# TKNTN.net
KiCad netlist of a schematic drawn in Altium Designer
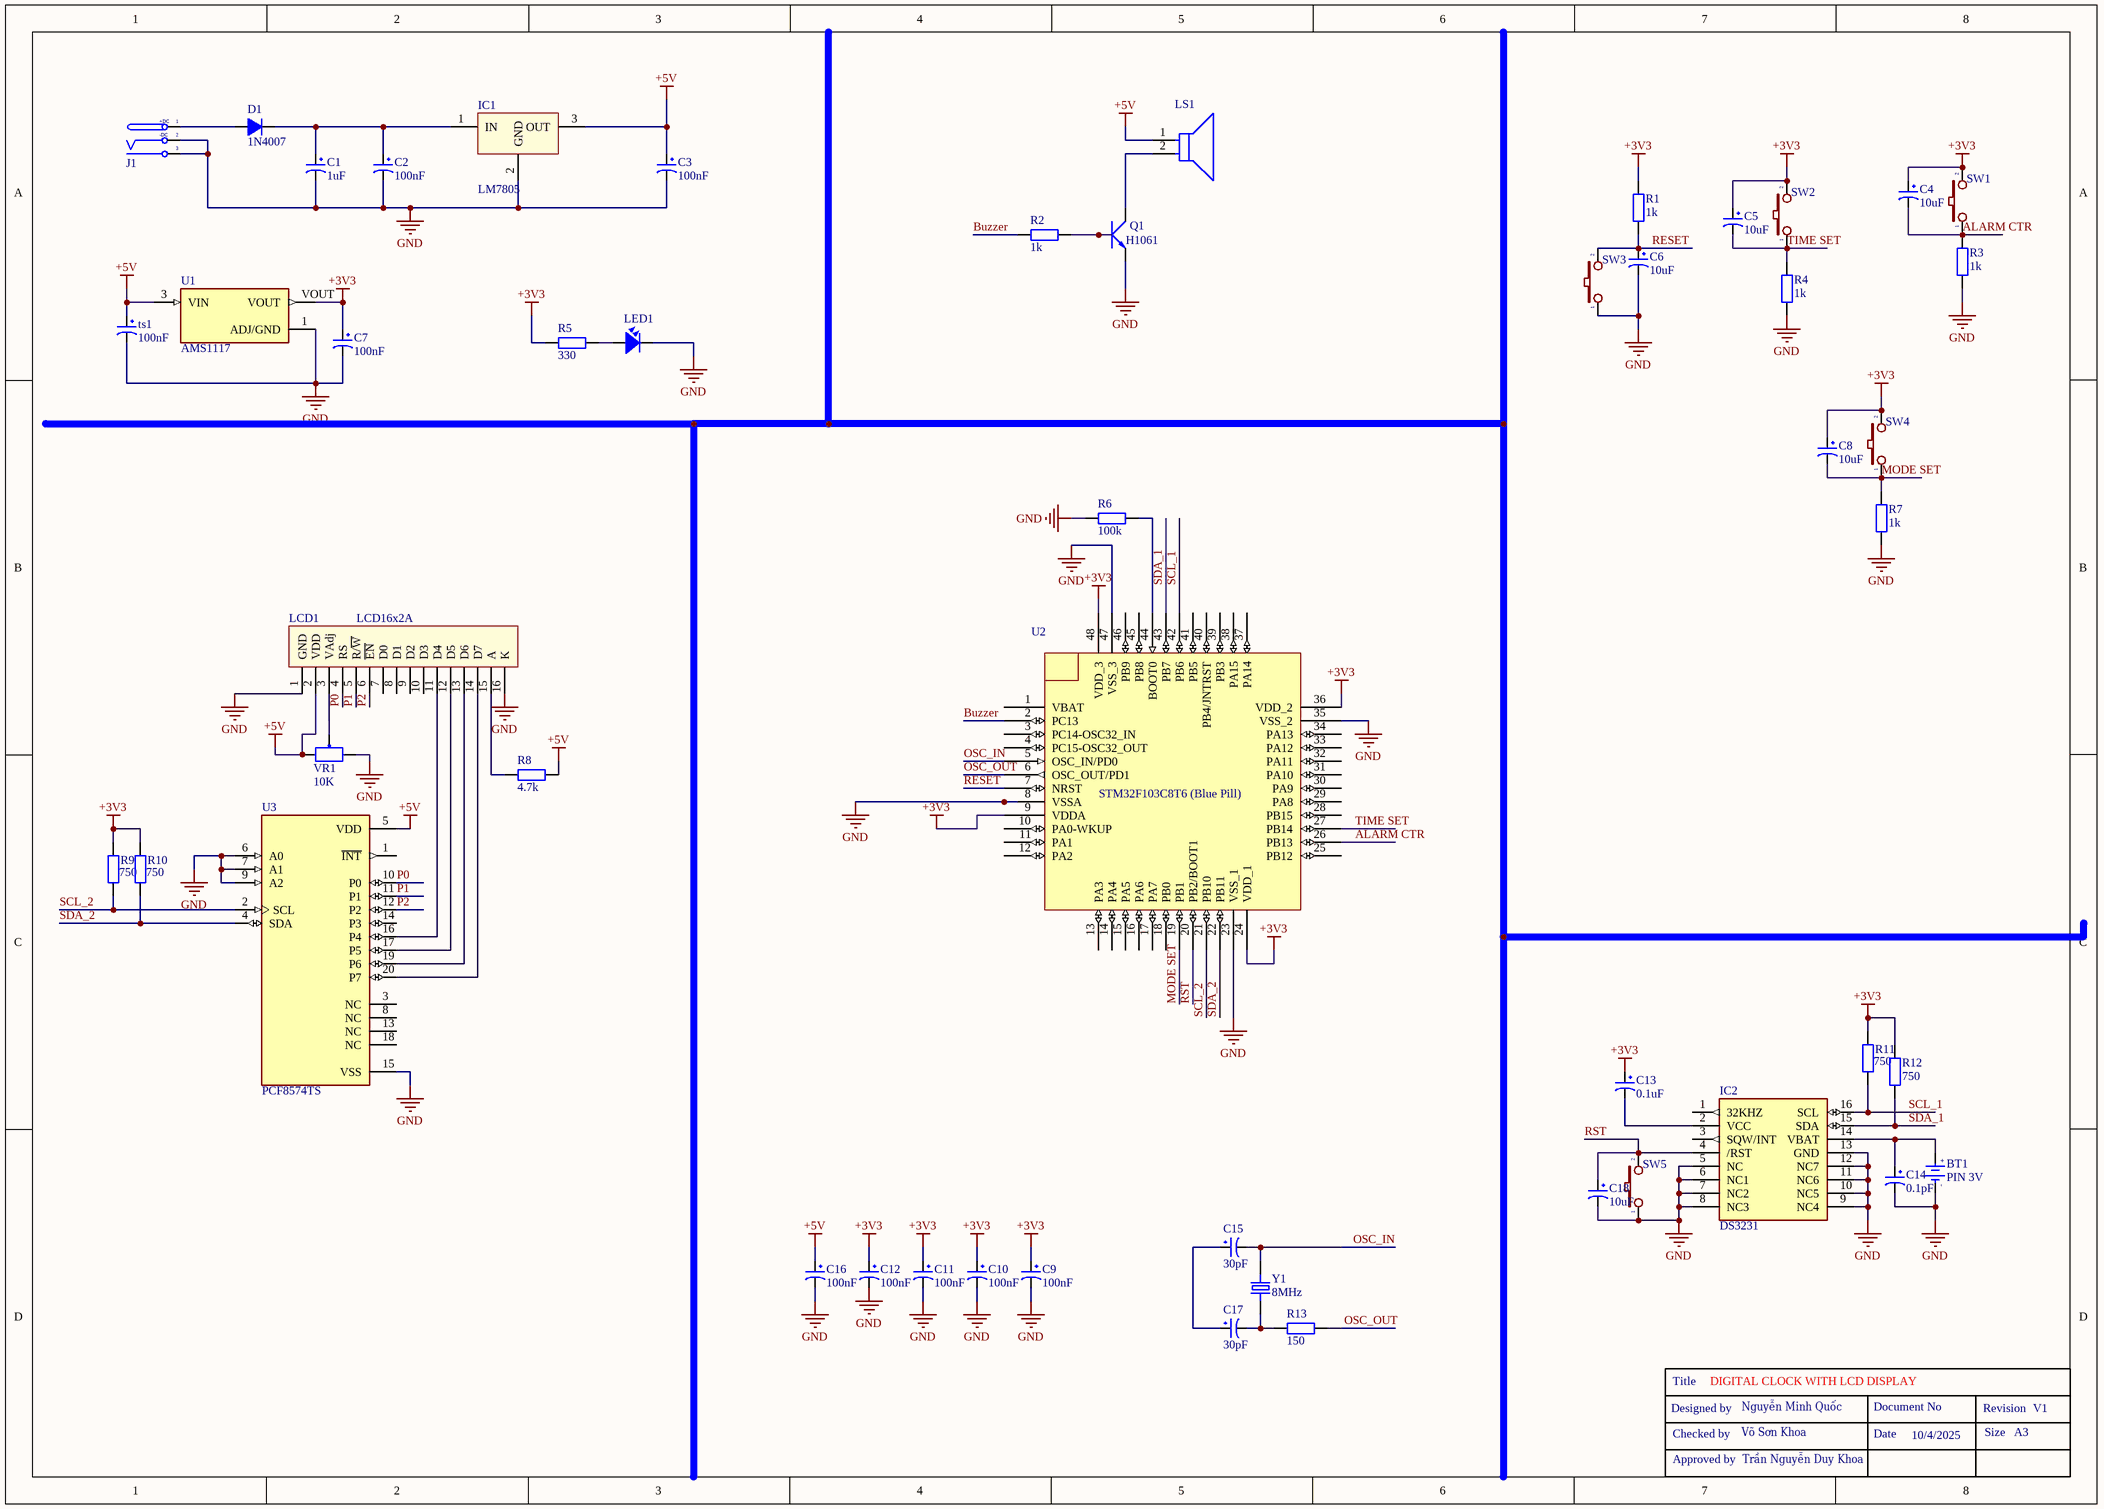
[diagram p0: TKNTN.SchDoc]

(export (version "E")
  (design (tool "Eeschema 10.0.6"))
  (components
    (comp (ref "*") (value "Component_2") (libsource (lib "Schlib1") (part "Component_2")))
    (comp (ref "BT1")
      (value "PIN 3V")
      (footprint "PIN3V")
      (description "Battery 3VDC")
      (libsource (lib "syhaunguyen") (part "PIN 3V"))
    )
    (comp (ref "C1")
      (value "1uF")
      (footprint "CP1/2")
      (description "Cap P  0,1uF < 22uF , 16 - 50V")
      (libsource (lib "syhaunguyen") (part "CP1"))
    )
    (comp (ref "C2")
      (value "100nF")
      (footprint "CP1/2")
      (description "Cap P  0,1uF < 22uF , 16 - 50V")
      (libsource (lib "syhaunguyen") (part "CP1"))
    )
    (comp (ref "C3")
      (value "100nF")
      (footprint "CP1/2")
      (description "Cap P  0,1uF < 22uF , 16 - 50V")
      (libsource (lib "syhaunguyen") (part "CP1"))
    )
    (comp (ref "C4")
      (value "10uF")
      (footprint "CP1/2")
      (description "Cap P  0,1uF < 22uF , 16 - 50V")
      (libsource (lib "syhaunguyen") (part "CP1"))
    )
    (comp (ref "C5")
      (value "10uF")
      (footprint "CP1/2")
      (description "Cap P  0,1uF < 22uF , 16 - 50V")
      (libsource (lib "syhaunguyen") (part "CP1"))
    )
    (comp (ref "C6")
      (value "10uF")
      (footprint "CP1/2")
      (description "Cap P  0,1uF < 22uF , 16 - 50V")
      (libsource (lib "syhaunguyen") (part "CP1"))
    )
    (comp (ref "C7")
      (value "100nF")
      (footprint "CP1/2")
      (description "Cap P  0,1uF < 22uF , 16 - 50V")
      (libsource (lib "syhaunguyen") (part "CP1"))
    )
    (comp (ref "C8")
      (value "10uF")
      (footprint "CP1/2")
      (description "Cap P  0,1uF < 22uF , 16 - 50V")
      (libsource (lib "syhaunguyen") (part "CP1"))
    )
    (comp (ref "C9")
      (value "100nF")
      (footprint "CP1/2")
      (description "Cap P  0,1uF < 22uF , 16 - 50V")
      (libsource (lib "syhaunguyen") (part "CP1"))
    )
    (comp (ref "C10")
      (value "100nF")
      (footprint "CP1/2")
      (description "Cap P  0,1uF < 22uF , 16 - 50V")
      (libsource (lib "syhaunguyen") (part "CP1"))
    )
    (comp (ref "C11")
      (value "100nF")
      (footprint "CP1/2")
      (description "Cap P  0,1uF < 22uF , 16 - 50V")
      (libsource (lib "syhaunguyen") (part "CP1"))
    )
    (comp (ref "C12")
      (value "100nF")
      (footprint "CP1/2")
      (description "Cap P  0,1uF < 22uF , 16 - 50V")
      (libsource (lib "syhaunguyen") (part "CP1"))
    )
    (comp (ref "C13")
      (value "0.1uF")
      (footprint "CP1/2")
      (description "Cap P  0,1uF < 22uF , 16 - 50V")
      (libsource (lib "syhaunguyen") (part "CP1"))
    )
    (comp (ref "C14")
      (value "0.1pF")
      (footprint "CP1/2")
      (description "Cap P  0,1uF < 22uF , 16 - 50V")
      (libsource (lib "syhaunguyen") (part "CP1"))
    )
    (comp (ref "C15")
      (value "30pF")
      (footprint "CP1/2")
      (description "Cap P  0,1uF < 22uF , 16 - 50V")
      (libsource (lib "") (part "CP1_1"))
    )
    (comp (ref "C16")
      (value "100nF")
      (footprint "CP1/2")
      (description "Cap P  0,1uF < 22uF , 16 - 50V")
      (libsource (lib "syhaunguyen") (part "CP1"))
    )
    (comp (ref "C17")
      (value "30pF")
      (footprint "CP1/2")
      (description "Cap P  0,1uF < 22uF , 16 - 50V")
      (libsource (lib "") (part "CP1_1"))
    )
    (comp (ref "C18")
      (value "10uF")
      (footprint "CP1/2")
      (description "Cap P  0,1uF < 22uF , 16 - 50V")
      (libsource (lib "syhaunguyen") (part "CP1"))
    )
    (comp (ref "D1")
      (value "1N4007")
      (footprint "D1A")
      (description "Diode 1A")
      (libsource (lib "syhaunguyen") (part "D1A"))
    )
    (comp (ref "IC1")
      (value "LM7805")
      (footprint "QTO-220")
      (description "On ap +, from + 5 to + 24VDC")
      (libsource (lib "syhaunguyen") (part "LM78xx"))
    )
    (comp (ref "IC2")
      (value "DS3231")
      (footprint "DS3231:SO16W")
      (description "Real Time Clock (RTC) IC Clock/Calendar - IÂ²C, 2-Wire Serial 8-SOIC (0.154, 3.90mm Width)")
      (fields (field (name "MF") "Maxim Integrated"))
      (libsource (lib "*") (part "DS3231"))
    )
    (comp (ref "J1")
      (value "JACK DC 5MM")
      (footprint "JACK DC 5MM")
      (libsource (lib "Cty1") (part "JACK DC 5MM"))
    )
    (comp (ref "LCD1")
      (value "LCD16x2A")
      (footprint "LCD16X2")
      (description "LCD dipslay 16 char, 2 line")
      (libsource (lib "my Library") (part "LCD16x2"))
    )
    (comp (ref "LED1")
      (value "LED")
      (footprint "LED-3")
      (description "LED Single colour Green and Red")
      (libsource (lib "syhaunguyen") (part "LED"))
    )
    (comp (ref "LS1")
      (value "PKM13EPYH4000-A0")
      (footprint "FP-PKM13EPYH4000-A0-MFG")
      (description "AUDIO PIEZO TRANSDUCER 30V TH")
      (libsource (lib "Altium Content Vault") (part "5f581d31613f872430949aa526fd155"))
    )
    (comp (ref "Q1")
      (value "H1061")
      (footprint "QTO-220")
      (description "P 1W, BCE")
      (libsource (lib "syhaunguyen") (part "NPN_BCE"))
    )
    (comp (ref "R1")
      (value "1k")
      (footprint "R1/4W")
      (description "Resistor 1/4W")
      (libsource (lib "syhaunguyen") (part "R1/4W"))
    )
    (comp (ref "R2")
      (value "1k")
      (footprint "R1/4W")
      (description "Resistor 1/4W")
      (libsource (lib "syhaunguyen") (part "R1/4W"))
    )
    (comp (ref "R3")
      (value "1k")
      (footprint "R1/4W")
      (description "Resistor 1/4W")
      (libsource (lib "syhaunguyen") (part "R1/4W"))
    )
    (comp (ref "R4")
      (value "1k")
      (footprint "R1/4W")
      (description "Resistor 1/4W")
      (libsource (lib "syhaunguyen") (part "R1/4W"))
    )
    (comp (ref "R5")
      (value "330")
      (footprint "R1/4W")
      (description "Resistor 1/4W")
      (libsource (lib "syhaunguyen") (part "R1/4W"))
    )
    (comp (ref "R6")
      (value "100k")
      (footprint "R1/4W")
      (description "Resistor 1/4W")
      (libsource (lib "syhaunguyen") (part "R1/4W"))
    )
    (comp (ref "R7")
      (value "1k")
      (footprint "R1/4W")
      (description "Resistor 1/4W")
      (libsource (lib "syhaunguyen") (part "R1/4W"))
    )
    (comp (ref "R8")
      (value "4.7k")
      (footprint "R1/4W")
      (description "Resistor 1/4W")
      (libsource (lib "syhaunguyen") (part "R1/4W"))
    )
    (comp (ref "R9")
      (value "750")
      (footprint "R1/4W")
      (description "Resistor 1/4W")
      (libsource (lib "syhaunguyen") (part "R1/4W"))
    )
    (comp (ref "R10")
      (value "750")
      (footprint "R1/4W")
      (description "Resistor 1/4W")
      (libsource (lib "syhaunguyen") (part "R1/4W"))
    )
    (comp (ref "R11")
      (value "750")
      (footprint "R1/4W")
      (description "Resistor 1/4W")
      (libsource (lib "syhaunguyen") (part "R1/4W"))
    )
    (comp (ref "R12")
      (value "750")
      (footprint "R1/4W")
      (description "Resistor 1/4W")
      (libsource (lib "syhaunguyen") (part "R1/4W"))
    )
    (comp (ref "R13")
      (value "150")
      (footprint "R1/4W")
      (description "Resistor 1/4W")
      (libsource (lib "syhaunguyen") (part "R1/4W"))
    )
    (comp (ref "SW1")
      (value "ALARM CTR")
      (footprint "SW2")
      (description "Switch button 2 pin")
      (libsource (lib "Cty1") (part "SW2"))
    )
    (comp (ref "SW2")
      (value "TIME SET")
      (footprint "SW2")
      (description "Switch button 2 pin")
      (libsource (lib "Cty1") (part "SW2"))
    )
    (comp (ref "SW3")
      (value "RESET")
      (footprint "SW2")
      (description "Switch button 2 pin")
      (libsource (lib "Cty1") (part "SW2"))
    )
    (comp (ref "SW4")
      (value "MODE SET")
      (footprint "SW2")
      (description "Switch button 2 pin")
      (libsource (lib "Cty1") (part "SW2"))
    )
    (comp (ref "SW5")
      (value "RST DS3221")
      (footprint "SW2")
      (description "Switch button 2 pin")
      (libsource (lib "Cty1") (part "SW2"))
    )
    (comp (ref "ts1")
      (value "100nF")
      (footprint "CP1/2")
      (description "Cap P  0,1uF < 22uF , 16 - 50V")
      (libsource (lib "syhaunguyen") (part "CP1"))
    )
    (comp (ref "U1")
      (value "AMS1117")
      (footprint "AMS1117:SOT229P700X180-4N")
      (description "1A LOW DROPOUT VOLTAGE REGULATOR SOT-223")
      (fields (field (name "MF") "Advanced Monolithic Systems"))
      (libsource (lib "*") (part "AMS1117"))
    )
    (comp (ref "U2")
      (value "STM32F103C8T6 (Blue Pill)")
      (footprint "STM32F103RC_TSQFP")
      (description "STM32 ARM-based 32-bit MCU with 64 Kbytes Flash, 48-pin LQFP, Industrial Temperature")
      (fields (field (name "PUBLISHER") "Altium Limited"))
      (libsource (lib "my Library") (part "STM32F103xx_LQFP48"))
    )
    (comp (ref "U3")
      (value "PCF8574TS")
      (footprint "PCF8574TS:SOP65P640X150-20N")
      (description "I/O Expander 8 IÂ²C 100 kHz 20-SSOP")
      (fields (field (name "MF") "NXP USA"))
      (libsource (lib "*") (part "PCF8574TS"))
    )
    (comp (ref "VR1")
      (value "10K")
      (footprint "VR")
      (description "Var Resistor")
      (libsource (lib "syhaunguyen") (part "VR"))
    )
    (comp (ref "Y1")
      (value "8MHz")
      (footprint "ECS_240_0001_18_1X:XTAL_ECS-200-20-1X")
      (description "Crystals / Oscillators / Resonators 24.00014MHz 18pF")
      (fields (field (name "MF") "ECS International") (field (name "MP") "ECS-240.0001-18-1X"))
      (libsource (lib "*") (part "ECS-240.0001-18-1X"))
    )
  )
  (nets
    (net (code "1") (name "+3V3") (class "Default")
      (node (ref "C10") (pin "1") (pinfunction "1_1") (pintype "passive"))
      (node (ref "C11") (pin "1") (pinfunction "1_1") (pintype "passive"))
      (node (ref "C12") (pin "1") (pinfunction "1_1") (pintype "passive"))
      (node (ref "C13") (pin "1") (pinfunction "1_1") (pintype "passive"))
      (node (ref "C4") (pin "1") (pinfunction "1_1") (pintype "passive"))
      (node (ref "C5") (pin "1") (pinfunction "1_1") (pintype "passive"))
      (node (ref "C7") (pin "1") (pinfunction "1_1") (pintype "passive"))
      (node (ref "C8") (pin "1") (pinfunction "1_1") (pintype "passive"))
      (node (ref "C9") (pin "1") (pinfunction "1_1") (pintype "passive"))
      (node (ref "R1") (pin "2") (pinfunction "2_2") (pintype "passive"))
      (node (ref "R10") (pin "2") (pinfunction "2_2") (pintype "passive"))
      (node (ref "R11") (pin "2") (pinfunction "2_2") (pintype "passive"))
      (node (ref "R12") (pin "2") (pinfunction "2_2") (pintype "passive"))
      (node (ref "R5") (pin "1") (pinfunction "1_1") (pintype "passive"))
      (node (ref "R9") (pin "2") (pinfunction "2_2") (pintype "passive"))
      (node (ref "SW1") (pin "2") (pinfunction "2_2") (pintype "passive"))
      (node (ref "SW2") (pin "2") (pinfunction "2_2") (pintype "passive"))
      (node (ref "SW4") (pin "2") (pinfunction "2_2") (pintype "passive"))
      (node (ref "U1") (pin "VOUT") (pinfunction "VOUT_VOUT") (pintype "output"))
      (node (ref "U2") (pin "24") (pinfunction "VDD_1_24") (pintype "power_in"))
      (node (ref "U2") (pin "36") (pinfunction "VDD_2_36") (pintype "power_in"))
      (node (ref "U2") (pin "48") (pinfunction "VDD_3_48") (pintype "power_in"))
      (node (ref "U2") (pin "9") (pinfunction "VDDA_9") (pintype "power_in"))
    )
    (net (code "2") (name "+5V") (class "Default")
      (node (ref "C16") (pin "1") (pinfunction "1_1") (pintype "passive"))
      (node (ref "C3") (pin "1") (pinfunction "1_1") (pintype "passive"))
      (node (ref "IC1") (pin "3") (pinfunction "OUT_3") (pintype "passive"))
      (node (ref "LCD1") (pin "2") (pinfunction "VDD_2") (pintype "passive"))
      (node (ref "LS1") (pin "1") (pinfunction "1_1") (pintype "passive"))
      (node (ref "R8") (pin "2") (pinfunction "2_2") (pintype "passive"))
      (node (ref "U1") (pin "3") (pinfunction "VIN_3") (pintype "input"))
      (node (ref "U3") (pin "5") (pinfunction "VDD_5") (pintype "power_in"))
      (node (ref "VR1") (pin "1") (pinfunction "1_1") (pintype "passive"))
      (node (ref "ts1") (pin "1") (pinfunction "1_1") (pintype "passive"))
    )
    (net (code "3") (name "/ALARM CTR") (class "Default")
      (node (ref "C4") (pin "2") (pinfunction "2_2") (pintype "passive"))
      (node (ref "R3") (pin "2") (pinfunction "2_2") (pintype "passive"))
      (node (ref "SW1") (pin "1") (pinfunction "1_1") (pintype "passive"))
      (node (ref "U2") (pin "26") (pinfunction "PB13_26") (pintype "bidirectional"))
    )
    (net (code "4") (name "/Buzzer") (class "Default")
      (node (ref "R2") (pin "1") (pinfunction "1_1") (pintype "passive"))
      (node (ref "U2") (pin "2") (pinfunction "PC13_2") (pintype "bidirectional"))
    )
    (net (code "5") (name "/MODE SET") (class "Default")
      (node (ref "C8") (pin "2") (pinfunction "2_2") (pintype "passive"))
      (node (ref "R7") (pin "2") (pinfunction "2_2") (pintype "passive"))
      (node (ref "SW4") (pin "1") (pinfunction "1_1") (pintype "passive"))
      (node (ref "U2") (pin "19") (pinfunction "PB1_19") (pintype "bidirectional"))
    )
    (net (code "6") (name "/OSC_IN") (class "Default")
      (node (ref "C15") (pin "2") (pinfunction "2_2") (pintype "passive"))
      (node (ref "U2") (pin "5") (pinfunction "OSC_IN/PD0_5") (pintype "input"))
      (node (ref "Y1") (pin "2") (pinfunction "2_2") (pintype "passive"))
    )
    (net (code "7") (name "/OSC_OUT") (class "Default")
      (node (ref "R13") (pin "2") (pinfunction "2_2") (pintype "passive"))
      (node (ref "U2") (pin "6") (pinfunction "OSC_OUT/PD1_6") (pintype "output"))
    )
    (net (code "8") (name "/P0") (class "Default")
      (node (ref "LCD1") (pin "4") (pinfunction "RS_4") (pintype "passive"))
      (node (ref "U3") (pin "10") (pinfunction "P0_10") (pintype "bidirectional"))
    )
    (net (code "9") (name "/P1") (class "Default")
      (node (ref "LCD1") (pin "5") (pinfunction "R/~{W}_5") (pintype "passive"))
      (node (ref "U3") (pin "11") (pinfunction "P1_11") (pintype "bidirectional"))
    )
    (net (code "10") (name "/P2") (class "Default")
      (node (ref "LCD1") (pin "6") (pinfunction "~{EN}_6") (pintype "passive"))
      (node (ref "U3") (pin "12") (pinfunction "P2_12") (pintype "bidirectional"))
    )
    (net (code "11") (name "/RESET") (class "Default")
      (node (ref "C6") (pin "1") (pinfunction "1_1") (pintype "passive"))
      (node (ref "R1") (pin "1") (pinfunction "1_1") (pintype "passive"))
      (node (ref "SW3") (pin "2") (pinfunction "2_2") (pintype "passive"))
      (node (ref "U2") (pin "7") (pinfunction "NRST_7") (pintype "bidirectional"))
    )
    (net (code "12") (name "/RST") (class "Default")
      (node (ref "C18") (pin "1") (pinfunction "1_1") (pintype "passive"))
      (node (ref "IC2") (pin "4") (pinfunction "/RST_4") (pintype "passive"))
      (node (ref "SW5") (pin "2") (pinfunction "2_2") (pintype "passive"))
      (node (ref "U2") (pin "20") (pinfunction "PB2/BOOT1_20") (pintype "bidirectional"))
    )
    (net (code "13") (name "/SCL_1") (class "Default")
      (node (ref "IC2") (pin "16") (pinfunction "SCL_16") (pintype "bidirectional"))
      (node (ref "R11") (pin "1") (pinfunction "1_1") (pintype "passive"))
      (node (ref "U2") (pin "42") (pinfunction "PB6_42") (pintype "bidirectional"))
    )
    (net (code "14") (name "/SCL_2") (class "Default")
      (node (ref "R9") (pin "1") (pinfunction "1_1") (pintype "passive"))
      (node (ref "U2") (pin "21") (pinfunction "PB10_21") (pintype "bidirectional"))
      (node (ref "U3") (pin "2") (pinfunction "SCL_2") (pintype "input"))
    )
    (net (code "15") (name "/SDA_1") (class "Default")
      (node (ref "IC2") (pin "15") (pinfunction "SDA_15") (pintype "bidirectional"))
      (node (ref "R12") (pin "1") (pinfunction "1_1") (pintype "passive"))
      (node (ref "U2") (pin "43") (pinfunction "PB7_43") (pintype "bidirectional"))
    )
    (net (code "16") (name "/SDA_2") (class "Default")
      (node (ref "R10") (pin "1") (pinfunction "1_1") (pintype "passive"))
      (node (ref "U2") (pin "22") (pinfunction "PB11_22") (pintype "bidirectional"))
      (node (ref "U3") (pin "4") (pinfunction "SDA_4") (pintype "bidirectional"))
    )
    (net (code "17") (name "/TIME SET") (class "Default")
      (node (ref "C5") (pin "2") (pinfunction "2_2") (pintype "passive"))
      (node (ref "R4") (pin "2") (pinfunction "2_2") (pintype "passive"))
      (node (ref "SW2") (pin "1") (pinfunction "1_1") (pintype "passive"))
      (node (ref "U2") (pin "27") (pinfunction "PB14_27") (pintype "bidirectional"))
    )
    (net (code "18") (name "GND") (class "Default")
      (node (ref "BT1") (pin "2") (pinfunction "GND_2") (pintype "passive"))
      (node (ref "C1") (pin "2") (pinfunction "2_2") (pintype "passive"))
      (node (ref "C10") (pin "2") (pinfunction "2_2") (pintype "passive"))
      (node (ref "C11") (pin "2") (pinfunction "2_2") (pintype "passive"))
      (node (ref "C12") (pin "2") (pinfunction "2_2") (pintype "passive"))
      (node (ref "C14") (pin "2") (pinfunction "2_2") (pintype "passive"))
      (node (ref "C16") (pin "2") (pinfunction "2_2") (pintype "passive"))
      (node (ref "C18") (pin "2") (pinfunction "2_2") (pintype "passive"))
      (node (ref "C2") (pin "2") (pinfunction "2_2") (pintype "passive"))
      (node (ref "C3") (pin "2") (pinfunction "2_2") (pintype "passive"))
      (node (ref "C6") (pin "2") (pinfunction "2_2") (pintype "passive"))
      (node (ref "C7") (pin "2") (pinfunction "2_2") (pintype "passive"))
      (node (ref "C9") (pin "2") (pinfunction "2_2") (pintype "passive"))
      (node (ref "IC1") (pin "2") (pinfunction "GND_2") (pintype "passive"))
      (node (ref "IC2") (pin "10") (pinfunction "NC5_10") (pintype "passive"))
      (node (ref "IC2") (pin "11") (pinfunction "NC6_11") (pintype "passive"))
      (node (ref "IC2") (pin "12") (pinfunction "NC7_12") (pintype "passive"))
      (node (ref "IC2") (pin "13") (pinfunction "GND_13") (pintype "power_in"))
      (node (ref "IC2") (pin "5") (pinfunction "NC_5") (pintype "passive"))
      (node (ref "IC2") (pin "6") (pinfunction "NC1_6") (pintype "passive"))
      (node (ref "IC2") (pin "7") (pinfunction "NC2_7") (pintype "passive"))
      (node (ref "IC2") (pin "8") (pinfunction "NC3_8") (pintype "passive"))
      (node (ref "IC2") (pin "9") (pinfunction "NC4_9") (pintype "passive"))
      (node (ref "J1") (pin "2") (pinfunction "TN_2") (pintype "passive"))
      (node (ref "J1") (pin "3") (pinfunction "S_3") (pintype "power_in"))
      (node (ref "LCD1") (pin "1") (pinfunction "GND_1") (pintype "passive"))
      (node (ref "LCD1") (pin "16") (pinfunction "K_16") (pintype "passive"))
      (node (ref "LED1") (pin "2") (pinfunction "2_2") (pintype "passive"))
      (node (ref "Q1") (pin "3") (pinfunction "E_3") (pintype "passive"))
      (node (ref "R3") (pin "1") (pinfunction "1_1") (pintype "passive"))
      (node (ref "R4") (pin "1") (pinfunction "1_1") (pintype "passive"))
      (node (ref "R6") (pin "1") (pinfunction "1_1") (pintype "passive"))
      (node (ref "R7") (pin "1") (pinfunction "1_1") (pintype "passive"))
      (node (ref "SW3") (pin "1") (pinfunction "1_1") (pintype "passive"))
      (node (ref "SW5") (pin "1") (pinfunction "1_1") (pintype "passive"))
      (node (ref "U1") (pin "1") (pinfunction "ADJ/GND_1") (pintype "power_in"))
      (node (ref "U2") (pin "23") (pinfunction "VSS_1_23") (pintype "power_in"))
      (node (ref "U2") (pin "35") (pinfunction "VSS_2_35") (pintype "power_in"))
      (node (ref "U2") (pin "47") (pinfunction "VSS_3_47") (pintype "power_in"))
      (node (ref "U2") (pin "8") (pinfunction "VSSA_8") (pintype "power_in"))
      (node (ref "U3") (pin "15") (pinfunction "VSS_15") (pintype "power_in"))
      (node (ref "U3") (pin "6") (pinfunction "A0_6") (pintype "input"))
      (node (ref "U3") (pin "7") (pinfunction "A1_7") (pintype "input"))
      (node (ref "U3") (pin "9") (pinfunction "A2_9") (pintype "input"))
      (node (ref "VR1") (pin "3") (pinfunction "3_3") (pintype "passive"))
      (node (ref "ts1") (pin "2") (pinfunction "2_2") (pintype "passive"))
    )
    (net (code "19") (name "Net-(BT1-+3V)") (class "Default")
      (node (ref "BT1") (pin "1") (pinfunction "+3V_1") (pintype "passive"))
      (node (ref "C14") (pin "1") (pinfunction "1_1") (pintype "passive"))
      (node (ref "IC2") (pin "14") (pinfunction "VBAT_14") (pintype "power_in"))
    )
    (net (code "20") (name "Net-(C15-Pad1)") (class "Default")
      (node (ref "C15") (pin "1") (pinfunction "1_1") (pintype "passive"))
      (node (ref "C17") (pin "1") (pinfunction "1_1") (pintype "passive"))
    )
    (net (code "21") (name "Net-(C17-Pad2)") (class "Default")
      (node (ref "C17") (pin "2") (pinfunction "2_2") (pintype "passive"))
      (node (ref "R13") (pin "1") (pinfunction "1_1") (pintype "passive"))
      (node (ref "Y1") (pin "1") (pinfunction "1_1") (pintype "passive"))
    )
    (net (code "22") (name "Net-(D1-A)") (class "Default")
      (node (ref "D1") (pin "1") (pinfunction "A_1") (pintype "passive"))
      (node (ref "J1") (pin "1") (pinfunction "T_1") (pintype "passive"))
    )
    (net (code "23") (name "Net-(D1-K)") (class "Default")
      (node (ref "C1") (pin "1") (pinfunction "1_1") (pintype "passive"))
      (node (ref "C2") (pin "1") (pinfunction "1_1") (pintype "passive"))
      (node (ref "D1") (pin "2") (pinfunction "K_2") (pintype "passive"))
      (node (ref "IC1") (pin "1") (pinfunction "IN_1") (pintype "passive"))
    )
    (net (code "24") (name "Net-(IC2-VCC)") (class "Default")
      (node (ref "C13") (pin "2") (pinfunction "2_2") (pintype "passive"))
      (node (ref "IC2") (pin "2") (pinfunction "VCC_2") (pintype "power_in"))
    )
    (net (code "25") (name "Net-(LCD1-A)") (class "Default")
      (node (ref "LCD1") (pin "15") (pinfunction "A_15") (pintype "passive"))
      (node (ref "R8") (pin "1") (pinfunction "1_1") (pintype "passive"))
    )
    (net (code "26") (name "Net-(LCD1-D4)") (class "Default")
      (node (ref "LCD1") (pin "11") (pinfunction "D4_11") (pintype "passive"))
      (node (ref "U3") (pin "16") (pinfunction "P4_16") (pintype "bidirectional"))
    )
    (net (code "27") (name "Net-(LCD1-D5)") (class "Default")
      (node (ref "LCD1") (pin "12") (pinfunction "D5_12") (pintype "passive"))
      (node (ref "U3") (pin "17") (pinfunction "P5_17") (pintype "bidirectional"))
    )
    (net (code "28") (name "Net-(LCD1-D6)") (class "Default")
      (node (ref "LCD1") (pin "13") (pinfunction "D6_13") (pintype "passive"))
      (node (ref "U3") (pin "19") (pinfunction "P6_19") (pintype "bidirectional"))
    )
    (net (code "29") (name "Net-(LCD1-D7)") (class "Default")
      (node (ref "LCD1") (pin "14") (pinfunction "D7_14") (pintype "passive"))
      (node (ref "U3") (pin "20") (pinfunction "P7_20") (pintype "bidirectional"))
    )
    (net (code "30") (name "Net-(LCD1-VAdj)") (class "Default")
      (node (ref "LCD1") (pin "3") (pinfunction "VAdj_3") (pintype "passive"))
      (node (ref "VR1") (pin "2") (pinfunction "2_2") (pintype "passive"))
    )
    (net (code "31") (name "Net-(LED1-Pad1)") (class "Default")
      (node (ref "LED1") (pin "1") (pinfunction "1_1") (pintype "passive"))
      (node (ref "R5") (pin "2") (pinfunction "2_2") (pintype "passive"))
    )
    (net (code "32") (name "Net-(Q1-B)") (class "Default")
      (node (ref "Q1") (pin "1") (pinfunction "B_1") (pintype "passive"))
      (node (ref "R2") (pin "2") (pinfunction "2_2") (pintype "passive"))
    )
    (net (code "33") (name "Net-(Q1-C)") (class "Default")
      (node (ref "LS1") (pin "2") (pinfunction "2_2") (pintype "passive"))
      (node (ref "Q1") (pin "2") (pinfunction "C_2") (pintype "passive"))
    )
    (net (code "34") (name "Net-(U2-BOOT0)") (class "Default")
      (node (ref "R6") (pin "2") (pinfunction "2_2") (pintype "passive"))
      (node (ref "U2") (pin "44") (pinfunction "BOOT0_44") (pintype "input"))
    )
    (net (code "35") (name "unconnected-(IC2-32KHZ-Pad1)") (class "Default")
      (node (ref "IC2") (pin "1") (pinfunction "32KHZ_1") (pintype "output"))
    )
    (net (code "36") (name "unconnected-(IC2-SQW{slash}INT-Pad3)") (class "Default")
      (node (ref "IC2") (pin "3") (pinfunction "SQW/INT_3") (pintype "output"))
    )
    (net (code "37") (name "unconnected-(LCD1-D0-Pad7)") (class "Default")
      (node (ref "LCD1") (pin "7") (pinfunction "D0_7") (pintype "passive"))
    )
    (net (code "38") (name "unconnected-(LCD1-D1-Pad8)") (class "Default")
      (node (ref "LCD1") (pin "8") (pinfunction "D1_8") (pintype "passive"))
    )
    (net (code "39") (name "unconnected-(LCD1-D2-Pad9)") (class "Default")
      (node (ref "LCD1") (pin "9") (pinfunction "D2_9") (pintype "passive"))
    )
    (net (code "40") (name "unconnected-(LCD1-D3-Pad10)") (class "Default")
      (node (ref "LCD1") (pin "10") (pinfunction "D3_10") (pintype "passive"))
    )
    (net (code "41") (name "unconnected-(U2-PA0-WKUP-Pad10)") (class "Default")
      (node (ref "U2") (pin "10") (pinfunction "PA0-WKUP_10") (pintype "bidirectional"))
    )
    (net (code "42") (name "unconnected-(U2-PA1-Pad11)") (class "Default")
      (node (ref "U2") (pin "11") (pinfunction "PA1_11") (pintype "bidirectional"))
    )
    (net (code "43") (name "unconnected-(U2-PA2-Pad12)") (class "Default")
      (node (ref "U2") (pin "12") (pinfunction "PA2_12") (pintype "bidirectional"))
    )
    (net (code "44") (name "unconnected-(U2-PA3-Pad13)") (class "Default")
      (node (ref "U2") (pin "13") (pinfunction "PA3_13") (pintype "bidirectional"))
    )
    (net (code "45") (name "unconnected-(U2-PA4-Pad14)") (class "Default")
      (node (ref "U2") (pin "14") (pinfunction "PA4_14") (pintype "bidirectional"))
    )
    (net (code "46") (name "unconnected-(U2-PA5-Pad15)") (class "Default")
      (node (ref "U2") (pin "15") (pinfunction "PA5_15") (pintype "bidirectional"))
    )
    (net (code "47") (name "unconnected-(U2-PA6-Pad16)") (class "Default")
      (node (ref "U2") (pin "16") (pinfunction "PA6_16") (pintype "bidirectional"))
    )
    (net (code "48") (name "unconnected-(U2-PA7-Pad17)") (class "Default")
      (node (ref "U2") (pin "17") (pinfunction "PA7_17") (pintype "bidirectional"))
    )
    (net (code "49") (name "unconnected-(U2-PA8-Pad29)") (class "Default")
      (node (ref "U2") (pin "29") (pinfunction "PA8_29") (pintype "bidirectional"))
    )
    (net (code "50") (name "unconnected-(U2-PA9-Pad30)") (class "Default")
      (node (ref "U2") (pin "30") (pinfunction "PA9_30") (pintype "bidirectional"))
    )
    (net (code "51") (name "unconnected-(U2-PA10-Pad31)") (class "Default")
      (node (ref "U2") (pin "31") (pinfunction "PA10_31") (pintype "bidirectional"))
    )
    (net (code "52") (name "unconnected-(U2-PA11-Pad32)") (class "Default")
      (node (ref "U2") (pin "32") (pinfunction "PA11_32") (pintype "bidirectional"))
    )
    (net (code "53") (name "unconnected-(U2-PA12-Pad33)") (class "Default")
      (node (ref "U2") (pin "33") (pinfunction "PA12_33") (pintype "bidirectional"))
    )
    (net (code "54") (name "unconnected-(U2-PA13-Pad34)") (class "Default")
      (node (ref "U2") (pin "34") (pinfunction "PA13_34") (pintype "bidirectional"))
    )
    (net (code "55") (name "unconnected-(U2-PA14-Pad37)") (class "Default")
      (node (ref "U2") (pin "37") (pinfunction "PA14_37") (pintype "bidirectional"))
    )
    (net (code "56") (name "unconnected-(U2-PA15-Pad38)") (class "Default")
      (node (ref "U2") (pin "38") (pinfunction "PA15_38") (pintype "bidirectional"))
    )
    (net (code "57") (name "unconnected-(U2-PB0-Pad18)") (class "Default")
      (node (ref "U2") (pin "18") (pinfunction "PB0_18") (pintype "bidirectional"))
    )
    (net (code "58") (name "unconnected-(U2-PB3-Pad39)") (class "Default")
      (node (ref "U2") (pin "39") (pinfunction "PB3_39") (pintype "bidirectional"))
    )
    (net (code "59") (name "unconnected-(U2-PB4{slash}JNTRST-Pad40)") (class "Default")
      (node (ref "U2") (pin "40") (pinfunction "PB4/JNTRST_40") (pintype "bidirectional"))
    )
    (net (code "60") (name "unconnected-(U2-PB5-Pad41)") (class "Default")
      (node (ref "U2") (pin "41") (pinfunction "PB5_41") (pintype "bidirectional"))
    )
    (net (code "61") (name "unconnected-(U2-PB8-Pad45)") (class "Default")
      (node (ref "U2") (pin "45") (pinfunction "PB8_45") (pintype "bidirectional"))
    )
    (net (code "62") (name "unconnected-(U2-PB9-Pad46)") (class "Default")
      (node (ref "U2") (pin "46") (pinfunction "PB9_46") (pintype "bidirectional"))
    )
    (net (code "63") (name "unconnected-(U2-PB12-Pad25)") (class "Default")
      (node (ref "U2") (pin "25") (pinfunction "PB12_25") (pintype "bidirectional"))
    )
    (net (code "64") (name "unconnected-(U2-PB15-Pad28)") (class "Default")
      (node (ref "U2") (pin "28") (pinfunction "PB15_28") (pintype "bidirectional"))
    )
    (net (code "65") (name "unconnected-(U2-PC14-OSC32_IN-Pad3)") (class "Default")
      (node (ref "U2") (pin "3") (pinfunction "PC14-OSC32_IN_3") (pintype "bidirectional"))
    )
    (net (code "66") (name "unconnected-(U2-PC15-OSC32_OUT-Pad4)") (class "Default")
      (node (ref "U2") (pin "4") (pinfunction "PC15-OSC32_OUT_4") (pintype "bidirectional"))
    )
    (net (code "67") (name "unconnected-(U2-VBAT-Pad1)") (class "Default")
      (node (ref "U2") (pin "1") (pinfunction "VBAT_1") (pintype "power_in"))
    )
    (net (code "68") (name "unconnected-(U3-NC-Pad3)") (class "Default")
      (node (ref "U3") (pin "3") (pinfunction "NC_3") (pintype "passive"))
    )
    (net (code "69") (name "unconnected-(U3-NC-Pad8)") (class "Default")
      (node (ref "U3") (pin "8") (pinfunction "NC_8") (pintype "passive"))
    )
    (net (code "70") (name "unconnected-(U3-NC-Pad13)") (class "Default")
      (node (ref "U3") (pin "13") (pinfunction "NC_13") (pintype "passive"))
    )
    (net (code "71") (name "unconnected-(U3-NC-Pad18)") (class "Default")
      (node (ref "U3") (pin "18") (pinfunction "NC_18") (pintype "passive"))
    )
    (net (code "72") (name "unconnected-(U3-P3-Pad14)") (class "Default")
      (node (ref "U3") (pin "14") (pinfunction "P3_14") (pintype "bidirectional"))
    )
    (net (code "73") (name "unconnected-(U3-~{INT}-Pad1)") (class "Default")
      (node (ref "U3") (pin "1") (pinfunction "~{INT}_1") (pintype "output"))
    )
  )
)
